# d7sch.net
KiCad netlist of a schematic drawn in EAGLE
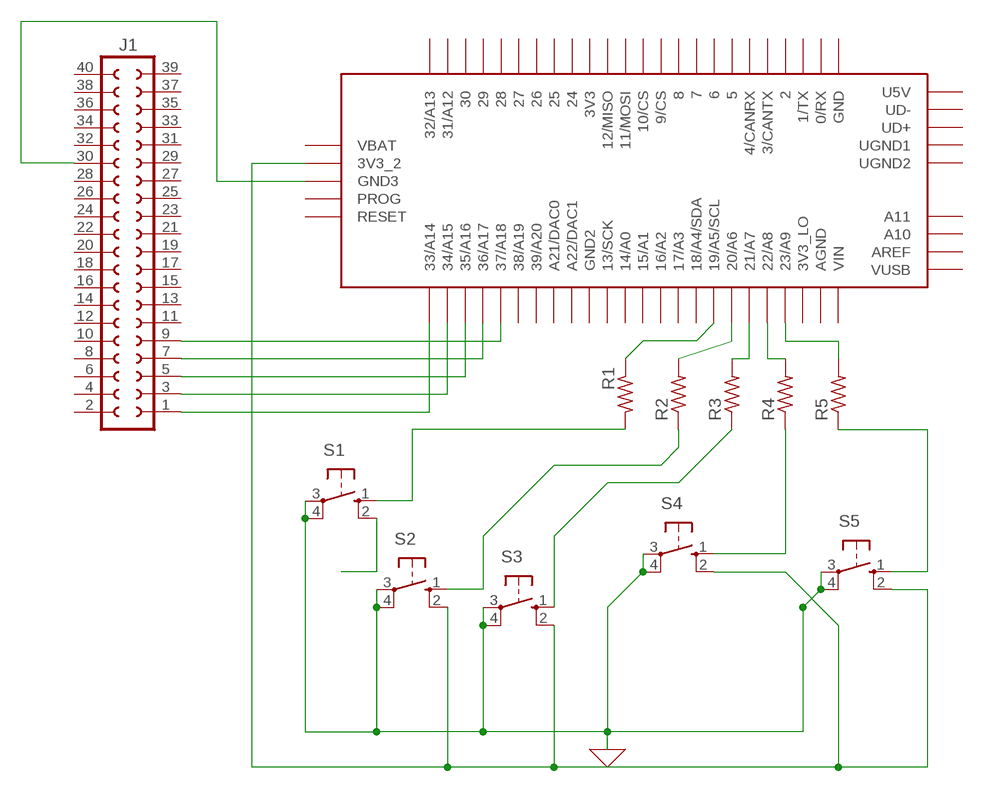
[diagram p0: schematic, sheet 1]

(export (version "E")
  (design (tool "Eeschema 10.0.6"))
  (components
    (comp (ref "J1")
      (value "SOCKET-40V")
      (footprint "eagle-import:S40V")
      (libsource (lib "eagle-import") (part "SOCKET-40V"))
    )
    (comp (ref "R1")
      (value "R-US_0204/2V")
      (footprint "eagle-import:0204V")
      (libsource (lib "eagle-import") (part "R-US_0204/2V"))
    )
    (comp (ref "R2")
      (value "R-US_0204/2V")
      (footprint "eagle-import:0204V")
      (libsource (lib "eagle-import") (part "R-US_0204/2V"))
    )
    (comp (ref "R3")
      (value "R-US_0204/2V")
      (footprint "eagle-import:0204V")
      (libsource (lib "eagle-import") (part "R-US_0204/2V"))
    )
    (comp (ref "R4")
      (value "R-US_0204/2V")
      (footprint "eagle-import:0204V")
      (libsource (lib "eagle-import") (part "R-US_0204/2V"))
    )
    (comp (ref "R5")
      (value "R-US_0204/2V")
      (footprint "eagle-import:0204V")
      (libsource (lib "eagle-import") (part "R-US_0204/2V"))
    )
    (comp (ref "S1")
      (value "10-XX")
      (footprint "eagle-import:B3F-10XX")
      (fields (field (name "MPN") "B3F-1000"))
      (libsource (lib "eagle-import") (part "10-XX"))
    )
    (comp (ref "S2")
      (value "10-XX")
      (footprint "eagle-import:B3F-10XX")
      (fields (field (name "MPN") "B3F-1000"))
      (libsource (lib "eagle-import") (part "10-XX"))
    )
    (comp (ref "S3")
      (value "10-XX")
      (footprint "eagle-import:B3F-10XX")
      (fields (field (name "MPN") "B3F-1000"))
      (libsource (lib "eagle-import") (part "10-XX"))
    )
    (comp (ref "S4")
      (value "10-XX")
      (footprint "eagle-import:B3F-10XX")
      (fields (field (name "MPN") "B3F-1000"))
      (libsource (lib "eagle-import") (part "10-XX"))
    )
    (comp (ref "S5")
      (value "10-XX")
      (footprint "eagle-import:B3F-10XX")
      (fields (field (name "MPN") "B3F-1000"))
      (libsource (lib "eagle-import") (part "10-XX"))
    )
    (comp (ref "U$1")
      (value "TEENSY_3.5/3.6")
      (footprint "eagle-import:TEENSY_3.5_3.6")
      (libsource (lib "eagle-import") (part "TEENSY_3.5/3.6"))
    )
  )
  (nets
    (net (code "1") (name "GND") (class "Default")
      (node (ref "S1") (pin "3") (pinfunction "P_3") (pintype "passive"))
      (node (ref "S1") (pin "4") (pinfunction "P1_4") (pintype "passive"))
      (node (ref "S2") (pin "3") (pinfunction "P_3") (pintype "passive"))
      (node (ref "S2") (pin "4") (pinfunction "P1_4") (pintype "passive"))
      (node (ref "S3") (pin "3") (pinfunction "P_3") (pintype "passive"))
      (node (ref "S3") (pin "4") (pinfunction "P1_4") (pintype "passive"))
      (node (ref "S4") (pin "3") (pinfunction "P_3") (pintype "passive"))
      (node (ref "S4") (pin "4") (pinfunction "P1_4") (pintype "passive"))
      (node (ref "S5") (pin "3") (pinfunction "P_3") (pintype "passive"))
      (node (ref "S5") (pin "4") (pinfunction "P1_4") (pintype "passive"))
    )
    (net (code "2") (name "Net-(J1-Pad1)") (class "Default")
      (node (ref "J1") (pin "1") (pinfunction "1_1") (pintype "passive"))
      (node (ref "U$1") (pin "33/A14") (pinfunction "33/A14_33/A14") (pintype "bidirectional"))
    )
    (net (code "3") (name "Net-(J1-Pad3)") (class "Default")
      (node (ref "J1") (pin "3") (pinfunction "3_3") (pintype "passive"))
      (node (ref "U$1") (pin "34/A15") (pinfunction "34/A15_34/A15") (pintype "bidirectional"))
    )
    (net (code "4") (name "Net-(J1-Pad5)") (class "Default")
      (node (ref "J1") (pin "5") (pinfunction "5_5") (pintype "passive"))
      (node (ref "U$1") (pin "35/A16") (pinfunction "35/A16_35/A16") (pintype "bidirectional"))
    )
    (net (code "5") (name "Net-(J1-Pad7)") (class "Default")
      (node (ref "J1") (pin "7") (pinfunction "7_7") (pintype "passive"))
      (node (ref "U$1") (pin "36/A17") (pinfunction "36/A17_36/A17") (pintype "bidirectional"))
    )
    (net (code "6") (name "Net-(J1-Pad9)") (class "Default")
      (node (ref "J1") (pin "9") (pinfunction "9_9") (pintype "passive"))
      (node (ref "U$1") (pin "37/A18") (pinfunction "37/A18_37/A18") (pintype "bidirectional"))
    )
    (net (code "7") (name "Net-(J1-Pad30)") (class "Default")
      (node (ref "J1") (pin "30") (pinfunction "30_30") (pintype "passive"))
      (node (ref "U$1") (pin "GND3") (pinfunction "GND3_GND3") (pintype "bidirectional"))
    )
    (net (code "8") (name "Net-(R1-Pad1)") (class "Default")
      (node (ref "R1") (pin "1") (pinfunction "1_1") (pintype "passive"))
      (node (ref "U$1") (pin "19/A5/SCL") (pinfunction "19/A5/SCL_19/A5/SCL") (pintype "bidirectional"))
    )
    (net (code "9") (name "Net-(R2-Pad2)") (class "Default")
      (node (ref "R2") (pin "2") (pinfunction "2_2") (pintype "passive"))
      (node (ref "U$1") (pin "20/A6") (pinfunction "20/A6_20/A6") (pintype "bidirectional"))
    )
    (net (code "10") (name "Net-(R3-Pad2)") (class "Default")
      (node (ref "R3") (pin "2") (pinfunction "2_2") (pintype "passive"))
      (node (ref "U$1") (pin "21/A7") (pinfunction "21/A7_21/A7") (pintype "bidirectional"))
    )
    (net (code "11") (name "Net-(R4-Pad2)") (class "Default")
      (node (ref "R4") (pin "2") (pinfunction "2_2") (pintype "passive"))
      (node (ref "U$1") (pin "22/A8") (pinfunction "22/A8_22/A8") (pintype "bidirectional"))
    )
    (net (code "12") (name "Net-(R5-Pad2)") (class "Default")
      (node (ref "R5") (pin "2") (pinfunction "2_2") (pintype "passive"))
      (node (ref "U$1") (pin "23/A9") (pinfunction "23/A9_23/A9") (pintype "bidirectional"))
    )
    (net (code "13") (name "Net-(S1-S)") (class "Default")
      (node (ref "R1") (pin "2") (pinfunction "2_2") (pintype "passive"))
      (node (ref "S1") (pin "1") (pinfunction "S_1") (pintype "passive"))
    )
    (net (code "14") (name "Net-(S2-S)") (class "Default")
      (node (ref "R2") (pin "1") (pinfunction "1_1") (pintype "passive"))
      (node (ref "S2") (pin "1") (pinfunction "S_1") (pintype "passive"))
    )
    (net (code "15") (name "Net-(S2-S1)") (class "Default")
      (node (ref "S2") (pin "2") (pinfunction "S1_2") (pintype "passive"))
      (node (ref "S3") (pin "2") (pinfunction "S1_2") (pintype "passive"))
      (node (ref "S4") (pin "2") (pinfunction "S1_2") (pintype "passive"))
      (node (ref "S5") (pin "2") (pinfunction "S1_2") (pintype "passive"))
      (node (ref "U$1") (pin "3V3_2") (pinfunction "3V3_2_3V3_2") (pintype "bidirectional"))
    )
    (net (code "16") (name "Net-(S3-S)") (class "Default")
      (node (ref "R3") (pin "1") (pinfunction "1_1") (pintype "passive"))
      (node (ref "S3") (pin "1") (pinfunction "S_1") (pintype "passive"))
    )
    (net (code "17") (name "Net-(S4-S)") (class "Default")
      (node (ref "R4") (pin "1") (pinfunction "1_1") (pintype "passive"))
      (node (ref "S4") (pin "1") (pinfunction "S_1") (pintype "passive"))
    )
    (net (code "18") (name "Net-(S5-S)") (class "Default")
      (node (ref "R5") (pin "1") (pinfunction "1_1") (pintype "passive"))
      (node (ref "S5") (pin "1") (pinfunction "S_1") (pintype "passive"))
    )
    (net (code "19") (name "unconnected-(J1-Pad2)") (class "Default")
      (node (ref "J1") (pin "2") (pinfunction "2_2") (pintype "passive"))
    )
    (net (code "20") (name "unconnected-(J1-Pad4)") (class "Default")
      (node (ref "J1") (pin "4") (pinfunction "4_4") (pintype "passive"))
    )
    (net (code "21") (name "unconnected-(J1-Pad6)") (class "Default")
      (node (ref "J1") (pin "6") (pinfunction "6_6") (pintype "passive"))
    )
    (net (code "22") (name "unconnected-(J1-Pad8)") (class "Default")
      (node (ref "J1") (pin "8") (pinfunction "8_8") (pintype "passive"))
    )
    (net (code "23") (name "unconnected-(J1-Pad10)") (class "Default")
      (node (ref "J1") (pin "10") (pinfunction "10_10") (pintype "passive"))
    )
    (net (code "24") (name "unconnected-(J1-Pad11)") (class "Default")
      (node (ref "J1") (pin "11") (pinfunction "11_11") (pintype "passive"))
    )
    (net (code "25") (name "unconnected-(J1-Pad12)") (class "Default")
      (node (ref "J1") (pin "12") (pinfunction "12_12") (pintype "passive"))
    )
    (net (code "26") (name "unconnected-(J1-Pad13)") (class "Default")
      (node (ref "J1") (pin "13") (pinfunction "13_13") (pintype "passive"))
    )
    (net (code "27") (name "unconnected-(J1-Pad14)") (class "Default")
      (node (ref "J1") (pin "14") (pinfunction "14_14") (pintype "passive"))
    )
    (net (code "28") (name "unconnected-(J1-Pad15)") (class "Default")
      (node (ref "J1") (pin "15") (pinfunction "15_15") (pintype "passive"))
    )
    (net (code "29") (name "unconnected-(J1-Pad16)") (class "Default")
      (node (ref "J1") (pin "16") (pinfunction "16_16") (pintype "passive"))
    )
    (net (code "30") (name "unconnected-(J1-Pad17)") (class "Default")
      (node (ref "J1") (pin "17") (pinfunction "17_17") (pintype "passive"))
    )
    (net (code "31") (name "unconnected-(J1-Pad18)") (class "Default")
      (node (ref "J1") (pin "18") (pinfunction "18_18") (pintype "passive"))
    )
    (net (code "32") (name "unconnected-(J1-Pad19)") (class "Default")
      (node (ref "J1") (pin "19") (pinfunction "19_19") (pintype "passive"))
    )
    (net (code "33") (name "unconnected-(J1-Pad20)") (class "Default")
      (node (ref "J1") (pin "20") (pinfunction "20_20") (pintype "passive"))
    )
    (net (code "34") (name "unconnected-(J1-Pad21)") (class "Default")
      (node (ref "J1") (pin "21") (pinfunction "21_21") (pintype "passive"))
    )
    (net (code "35") (name "unconnected-(J1-Pad22)") (class "Default")
      (node (ref "J1") (pin "22") (pinfunction "22_22") (pintype "passive"))
    )
    (net (code "36") (name "unconnected-(J1-Pad23)") (class "Default")
      (node (ref "J1") (pin "23") (pinfunction "23_23") (pintype "passive"))
    )
    (net (code "37") (name "unconnected-(J1-Pad24)") (class "Default")
      (node (ref "J1") (pin "24") (pinfunction "24_24") (pintype "passive"))
    )
    (net (code "38") (name "unconnected-(J1-Pad25)") (class "Default")
      (node (ref "J1") (pin "25") (pinfunction "25_25") (pintype "passive"))
    )
    (net (code "39") (name "unconnected-(J1-Pad26)") (class "Default")
      (node (ref "J1") (pin "26") (pinfunction "26_26") (pintype "passive"))
    )
    (net (code "40") (name "unconnected-(J1-Pad27)") (class "Default")
      (node (ref "J1") (pin "27") (pinfunction "27_27") (pintype "passive"))
    )
    (net (code "41") (name "unconnected-(J1-Pad28)") (class "Default")
      (node (ref "J1") (pin "28") (pinfunction "28_28") (pintype "passive"))
    )
    (net (code "42") (name "unconnected-(J1-Pad29)") (class "Default")
      (node (ref "J1") (pin "29") (pinfunction "29_29") (pintype "passive"))
    )
    (net (code "43") (name "unconnected-(J1-Pad31)") (class "Default")
      (node (ref "J1") (pin "31") (pinfunction "31_31") (pintype "passive"))
    )
    (net (code "44") (name "unconnected-(J1-Pad32)") (class "Default")
      (node (ref "J1") (pin "32") (pinfunction "32_32") (pintype "passive"))
    )
    (net (code "45") (name "unconnected-(J1-Pad33)") (class "Default")
      (node (ref "J1") (pin "33") (pinfunction "33_33") (pintype "passive"))
    )
    (net (code "46") (name "unconnected-(J1-Pad34)") (class "Default")
      (node (ref "J1") (pin "34") (pinfunction "34_34") (pintype "passive"))
    )
    (net (code "47") (name "unconnected-(J1-Pad35)") (class "Default")
      (node (ref "J1") (pin "35") (pinfunction "35_35") (pintype "passive"))
    )
    (net (code "48") (name "unconnected-(J1-Pad36)") (class "Default")
      (node (ref "J1") (pin "36") (pinfunction "36_36") (pintype "passive"))
    )
    (net (code "49") (name "unconnected-(J1-Pad37)") (class "Default")
      (node (ref "J1") (pin "37") (pinfunction "37_37") (pintype "passive"))
    )
    (net (code "50") (name "unconnected-(J1-Pad38)") (class "Default")
      (node (ref "J1") (pin "38") (pinfunction "38_38") (pintype "passive"))
    )
    (net (code "51") (name "unconnected-(J1-Pad39)") (class "Default")
      (node (ref "J1") (pin "39") (pinfunction "39_39") (pintype "passive"))
    )
    (net (code "52") (name "unconnected-(J1-Pad40)") (class "Default")
      (node (ref "J1") (pin "40") (pinfunction "40_40") (pintype "passive"))
    )
    (net (code "53") (name "unconnected-(S1-S1-Pad2)") (class "Default")
      (node (ref "S1") (pin "2") (pinfunction "S1_2") (pintype "passive"))
    )
    (net (code "54") (name "unconnected-(U$1-A21{slash}DAC0-Pad21{slash}DAC0)") (class "Default")
      (node (ref "U$1") (pin "21/DAC0") (pinfunction "A21/DAC0_21/DAC0") (pintype "bidirectional"))
    )
    (net (code "55") (name "unconnected-(U$1-Pad0{slash}RX)") (class "Default")
      (node (ref "U$1") (pin "0/RX") (pinfunction "0/RX_0/RX") (pintype "bidirectional"))
    )
    (net (code "56") (name "unconnected-(U$1-Pad1{slash}TX)") (class "Default")
      (node (ref "U$1") (pin "1/TX") (pinfunction "1/TX_1/TX") (pintype "bidirectional"))
    )
    (net (code "57") (name "unconnected-(U$1-Pad2)") (class "Default")
      (node (ref "U$1") (pin "2") (pinfunction "2_2") (pintype "bidirectional"))
    )
    (net (code "58") (name "unconnected-(U$1-Pad3V3)") (class "Default")
      (node (ref "U$1") (pin "3V3") (pinfunction "3V3_3V3") (pintype "bidirectional"))
    )
    (net (code "59") (name "unconnected-(U$1-Pad3V3_LO)") (class "Default")
      (node (ref "U$1") (pin "3V3_LO") (pinfunction "3V3_LO_3V3_LO") (pintype "bidirectional"))
    )
    (net (code "60") (name "unconnected-(U$1-Pad3{slash}CANTX)") (class "Default")
      (node (ref "U$1") (pin "3/CANTX") (pinfunction "3/CANTX_3/CANTX") (pintype "bidirectional"))
    )
    (net (code "61") (name "unconnected-(U$1-Pad4{slash}CANRX)") (class "Default")
      (node (ref "U$1") (pin "4/CANRX") (pinfunction "4/CANRX_4/CANRX") (pintype "bidirectional"))
    )
    (net (code "62") (name "unconnected-(U$1-Pad5)") (class "Default")
      (node (ref "U$1") (pin "5") (pinfunction "5_5") (pintype "bidirectional"))
    )
    (net (code "63") (name "unconnected-(U$1-Pad6)") (class "Default")
      (node (ref "U$1") (pin "6") (pinfunction "6_6") (pintype "bidirectional"))
    )
    (net (code "64") (name "unconnected-(U$1-Pad7)") (class "Default")
      (node (ref "U$1") (pin "7") (pinfunction "7_7") (pintype "bidirectional"))
    )
    (net (code "65") (name "unconnected-(U$1-Pad8)") (class "Default")
      (node (ref "U$1") (pin "8") (pinfunction "8_8") (pintype "bidirectional"))
    )
    (net (code "66") (name "unconnected-(U$1-Pad9{slash}CS)") (class "Default")
      (node (ref "U$1") (pin "9/CS") (pinfunction "9/CS_9/CS") (pintype "bidirectional"))
    )
    (net (code "67") (name "unconnected-(U$1-Pad10{slash}CS)") (class "Default")
      (node (ref "U$1") (pin "10/CS") (pinfunction "10/CS_10/CS") (pintype "bidirectional"))
    )
    (net (code "68") (name "unconnected-(U$1-Pad11{slash}MOSI)") (class "Default")
      (node (ref "U$1") (pin "11/MOSI") (pinfunction "11/MOSI_11/MOSI") (pintype "bidirectional"))
    )
    (net (code "69") (name "unconnected-(U$1-Pad12{slash}MISO)") (class "Default")
      (node (ref "U$1") (pin "12/MISO") (pinfunction "12/MISO_12/MISO") (pintype "bidirectional"))
    )
    (net (code "70") (name "unconnected-(U$1-Pad13{slash}SCK)") (class "Default")
      (node (ref "U$1") (pin "13/SCK") (pinfunction "13/SCK_13/SCK") (pintype "bidirectional"))
    )
    (net (code "71") (name "unconnected-(U$1-Pad14{slash}A0)") (class "Default")
      (node (ref "U$1") (pin "14/A0") (pinfunction "14/A0_14/A0") (pintype "bidirectional"))
    )
    (net (code "72") (name "unconnected-(U$1-Pad15{slash}A1)") (class "Default")
      (node (ref "U$1") (pin "15/A1") (pinfunction "15/A1_15/A1") (pintype "bidirectional"))
    )
    (net (code "73") (name "unconnected-(U$1-Pad16{slash}A2)") (class "Default")
      (node (ref "U$1") (pin "16/A2") (pinfunction "16/A2_16/A2") (pintype "bidirectional"))
    )
    (net (code "74") (name "unconnected-(U$1-Pad17{slash}A3)") (class "Default")
      (node (ref "U$1") (pin "17/A3") (pinfunction "17/A3_17/A3") (pintype "bidirectional"))
    )
    (net (code "75") (name "unconnected-(U$1-Pad18{slash}A4{slash}SDA)") (class "Default")
      (node (ref "U$1") (pin "18/A4/SDA") (pinfunction "18/A4/SDA_18/A4/SDA") (pintype "bidirectional"))
    )
    (net (code "76") (name "unconnected-(U$1-Pad24)") (class "Default")
      (node (ref "U$1") (pin "24") (pinfunction "24_24") (pintype "bidirectional"))
    )
    (net (code "77") (name "unconnected-(U$1-Pad25)") (class "Default")
      (node (ref "U$1") (pin "25") (pinfunction "25_25") (pintype "bidirectional"))
    )
    (net (code "78") (name "unconnected-(U$1-Pad26)") (class "Default")
      (node (ref "U$1") (pin "26") (pinfunction "26_26") (pintype "bidirectional"))
    )
    (net (code "79") (name "unconnected-(U$1-Pad27)") (class "Default")
      (node (ref "U$1") (pin "27") (pinfunction "27_27") (pintype "bidirectional"))
    )
    (net (code "80") (name "unconnected-(U$1-Pad28)") (class "Default")
      (node (ref "U$1") (pin "28") (pinfunction "28_28") (pintype "bidirectional"))
    )
    (net (code "81") (name "unconnected-(U$1-Pad29)") (class "Default")
      (node (ref "U$1") (pin "29") (pinfunction "29_29") (pintype "bidirectional"))
    )
    (net (code "82") (name "unconnected-(U$1-Pad30)") (class "Default")
      (node (ref "U$1") (pin "30") (pinfunction "30_30") (pintype "bidirectional"))
    )
    (net (code "83") (name "unconnected-(U$1-Pad31{slash}A12)") (class "Default")
      (node (ref "U$1") (pin "31/A12") (pinfunction "31/A12_31/A12") (pintype "bidirectional"))
    )
    (net (code "84") (name "unconnected-(U$1-Pad32{slash}A13)") (class "Default")
      (node (ref "U$1") (pin "32/A13") (pinfunction "32/A13_32/A13") (pintype "bidirectional"))
    )
    (net (code "85") (name "unconnected-(U$1-Pad38{slash}A19)") (class "Default")
      (node (ref "U$1") (pin "38/A19") (pinfunction "38/A19_38/A19") (pintype "bidirectional"))
    )
    (net (code "86") (name "unconnected-(U$1-Pad39{slash}A20)") (class "Default")
      (node (ref "U$1") (pin "39/A20") (pinfunction "39/A20_39/A20") (pintype "bidirectional"))
    )
    (net (code "87") (name "unconnected-(U$1-PadA10)") (class "Default")
      (node (ref "U$1") (pin "A10") (pinfunction "A10_A10") (pintype "bidirectional"))
    )
    (net (code "88") (name "unconnected-(U$1-PadA11)") (class "Default")
      (node (ref "U$1") (pin "A11") (pinfunction "A11_A11") (pintype "bidirectional"))
    )
    (net (code "89") (name "unconnected-(U$1-PadA22{slash}DAC1)") (class "Default")
      (node (ref "U$1") (pin "A22/DAC1") (pinfunction "A22/DAC1_A22/DAC1") (pintype "bidirectional"))
    )
    (net (code "90") (name "unconnected-(U$1-PadAGND)") (class "Default")
      (node (ref "U$1") (pin "AGND") (pinfunction "AGND_AGND") (pintype "bidirectional"))
    )
    (net (code "91") (name "unconnected-(U$1-PadAREF)") (class "Default")
      (node (ref "U$1") (pin "AREF") (pinfunction "AREF_AREF") (pintype "bidirectional"))
    )
    (net (code "92") (name "unconnected-(U$1-PadGND)") (class "Default")
      (node (ref "U$1") (pin "GND") (pinfunction "GND_GND") (pintype "bidirectional"))
    )
    (net (code "93") (name "unconnected-(U$1-PadGND2)") (class "Default")
      (node (ref "U$1") (pin "GND2") (pinfunction "GND2_GND2") (pintype "bidirectional"))
    )
    (net (code "94") (name "unconnected-(U$1-PadPROG)") (class "Default")
      (node (ref "U$1") (pin "PROG") (pinfunction "PROG_PROG") (pintype "bidirectional"))
    )
    (net (code "95") (name "unconnected-(U$1-PadRESET)") (class "Default")
      (node (ref "U$1") (pin "RESET") (pinfunction "RESET_RESET") (pintype "bidirectional"))
    )
    (net (code "96") (name "unconnected-(U$1-PadU5V)") (class "Default")
      (node (ref "U$1") (pin "U5V") (pinfunction "U5V_U5V") (pintype "bidirectional"))
    )
    (net (code "97") (name "unconnected-(U$1-PadUD+)") (class "Default")
      (node (ref "U$1") (pin "UD+") (pinfunction "UD+_UD+") (pintype "bidirectional"))
    )
    (net (code "98") (name "unconnected-(U$1-PadUD-)") (class "Default")
      (node (ref "U$1") (pin "UD-") (pinfunction "UD-_UD-") (pintype "bidirectional"))
    )
    (net (code "99") (name "unconnected-(U$1-PadUGND1)") (class "Default")
      (node (ref "U$1") (pin "UGND1") (pinfunction "UGND1_UGND1") (pintype "bidirectional"))
    )
    (net (code "100") (name "unconnected-(U$1-PadUGND2)") (class "Default")
      (node (ref "U$1") (pin "UGND2") (pinfunction "UGND2_UGND2") (pintype "bidirectional"))
    )
    (net (code "101") (name "unconnected-(U$1-PadVBAT)") (class "Default")
      (node (ref "U$1") (pin "VBAT") (pinfunction "VBAT_VBAT") (pintype "bidirectional"))
    )
    (net (code "102") (name "unconnected-(U$1-PadVIN)") (class "Default")
      (node (ref "U$1") (pin "VIN") (pinfunction "VIN_VIN") (pintype "bidirectional"))
    )
    (net (code "103") (name "unconnected-(U$1-PadVUSB)") (class "Default")
      (node (ref "U$1") (pin "VUSB") (pinfunction "VUSB_VUSB") (pintype "bidirectional"))
    )
  )
)
